# ATMEGA8_PLC.net
KiCad netlist of a schematic drawn in Altium Designer
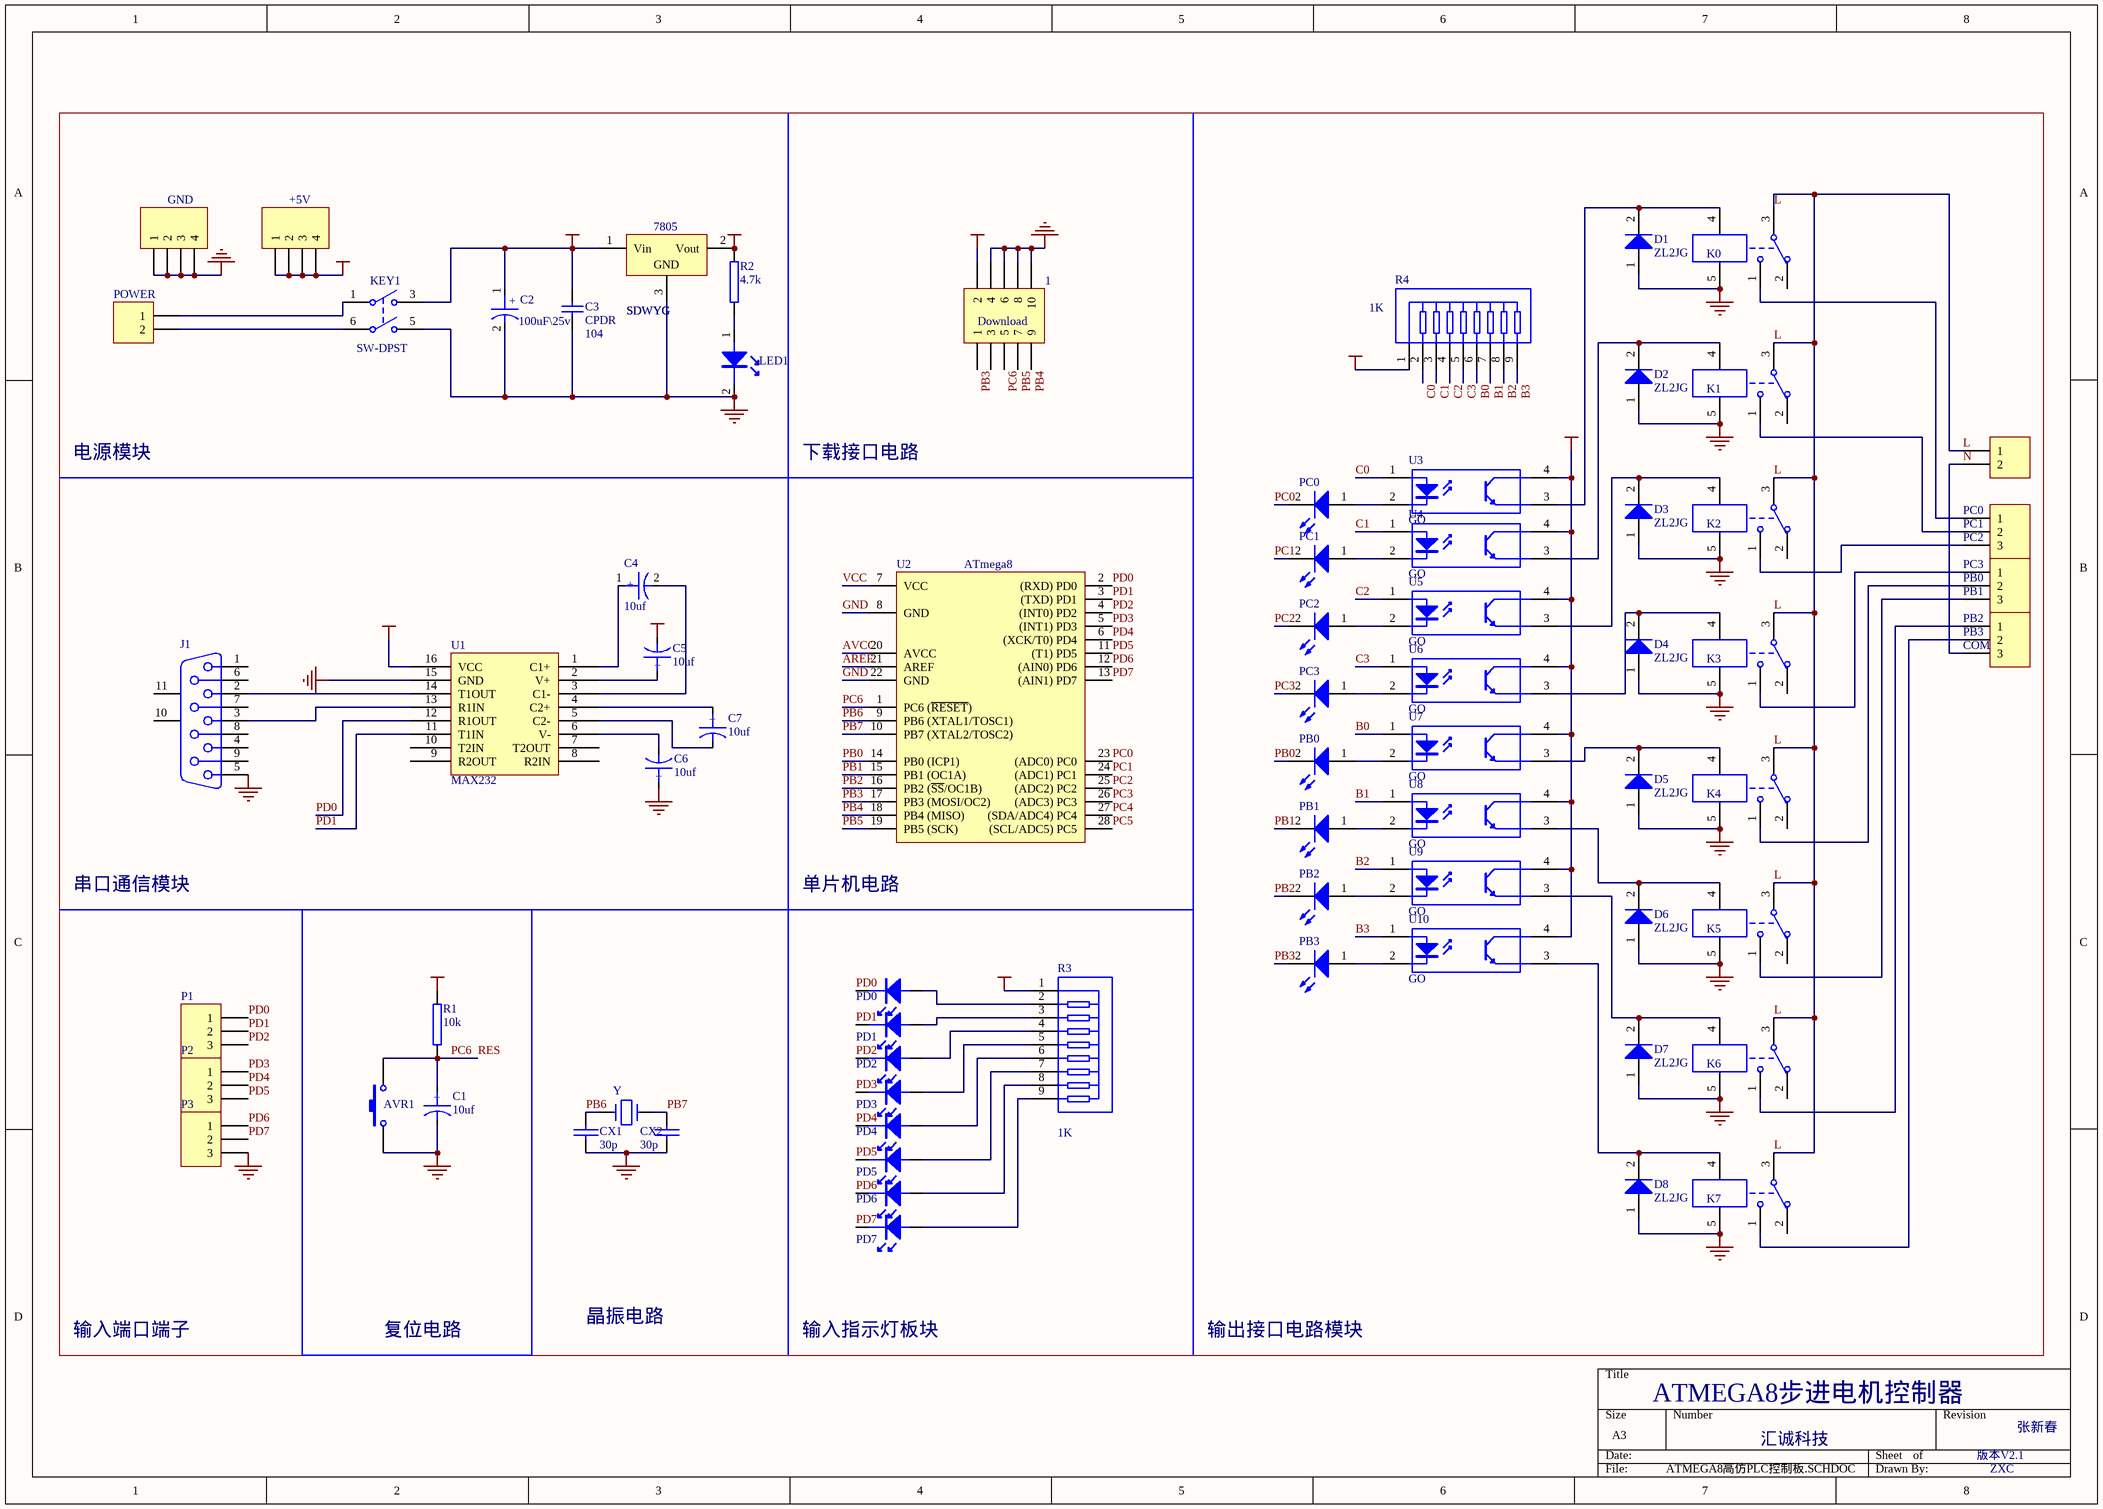
[diagram p0: ATMEGA8高仿PLC控制板.SCHDOC]

(export (version "E")
  (design (tool "Eeschema 10.0.6"))
  (components
    (comp (ref "+5V")
      (value "~")
      (footprint "HDR1X4")
      (description "Header, 4-Pin")
      (fields (field (name "PUBLISHER") "Altium Limited"))
      (libsource (lib "Miscellaneous Connectors") (part "Header 4"))
    )
    (comp (ref "1")
      (value "Download")
      (footprint "HDR-2x5")
      (description "Header, 5-Pin, Dual row")
      (fields (field (name "PUBLISHER") "Altium Limited"))
      (libsource (lib "Miscellaneous Connectors") (part "Header 5X2"))
    )
    (comp (ref "7805")
      (value "SDWYG")
      (footprint "wyk")
      (description "三端稳压器")
      (fields (field (name "PUBLISHER") "Altium Limited"))
      (libsource (lib "zxcourhc") (part "SDWYG"))
    )
    (comp (ref "AVR1")
      (value "~")
      (footprint "an-6*6")
      (description "Switch")
      (fields (field (name "PUBLISHER") "Altium Limited"))
      (libsource (lib "Miscellaneous Devices") (part "SW-PB"))
    )
    (comp (ref "C1")
      (value "10uf")
      (footprint "C-DJ-4")
      (description "Capacitor")
      (libsource (lib "") (part "CAPACITOR POL_1"))
    )
    (comp (ref "C2")
      (value "100u~{F}25v")
      (footprint "C-DJ-6")
      (description "Capacitor")
      (libsource (lib "OldCow1 (1)") (part "CAPACITOR POL"))
    )
    (comp (ref "C3")
      (value "CPDR")
      (footprint "CPDR")
      (description "瓷片电容")
      (fields (field (name "ALTIUM_VALUE") "104") (field (name "PUBLISHER") "Altium Limited"))
      (libsource (lib "zxcourhc") (part "CPDR"))
    )
    (comp (ref "C4")
      (value "10uf")
      (footprint "C-DJ-4")
      (description "Capacitor")
      (libsource (lib "*") (part "CAPACITOR POL"))
    )
    (comp (ref "C5")
      (value "10uf")
      (footprint "C-DJ-4")
      (description "Capacitor")
      (libsource (lib "") (part "CAPACITOR POL_1"))
    )
    (comp (ref "C6")
      (value "10uf")
      (footprint "C-DJ-4")
      (description "Capacitor")
      (libsource (lib "") (part "CAPACITOR POL_1"))
    )
    (comp (ref "C7")
      (value "10uf")
      (footprint "C-DJ-4")
      (description "Capacitor")
      (libsource (lib "") (part "CAPACITOR POL_1"))
    )
    (comp (ref "CX1")
      (value "30p")
      (footprint "HDR1X2")
      (description "Capacitor")
      (libsource (lib "*") (part "CAP"))
    )
    (comp (ref "CX2")
      (value "30p")
      (footprint "HDR1X2")
      (description "Capacitor")
      (libsource (lib "*") (part "CAP"))
    )
    (comp (ref "D1")
      (value "ZL2JG")
      (footprint "D-ZL-10")
      (description "整流二极管")
      (fields (field (name "PUBLISHER") "Altium Limited"))
      (libsource (lib "zxcourhc") (part "ZL2JG"))
    )
    (comp (ref "D2")
      (value "ZL2JG")
      (footprint "D-ZL-10")
      (description "整流二极管")
      (fields (field (name "PUBLISHER") "Altium Limited"))
      (libsource (lib "zxcourhc") (part "ZL2JG"))
    )
    (comp (ref "D3")
      (value "ZL2JG")
      (footprint "D-ZL-10")
      (description "整流二极管")
      (fields (field (name "PUBLISHER") "Altium Limited"))
      (libsource (lib "zxcourhc") (part "ZL2JG"))
    )
    (comp (ref "D4")
      (value "ZL2JG")
      (footprint "D-ZL-10")
      (description "整流二极管")
      (fields (field (name "PUBLISHER") "Altium Limited"))
      (libsource (lib "zxcourhc") (part "ZL2JG"))
    )
    (comp (ref "D5")
      (value "ZL2JG")
      (footprint "D-ZL-10")
      (description "整流二极管")
      (fields (field (name "PUBLISHER") "Altium Limited"))
      (libsource (lib "zxcourhc") (part "ZL2JG"))
    )
    (comp (ref "D6")
      (value "ZL2JG")
      (footprint "D-ZL-10")
      (description "整流二极管")
      (fields (field (name "PUBLISHER") "Altium Limited"))
      (libsource (lib "zxcourhc") (part "ZL2JG"))
    )
    (comp (ref "D7")
      (value "ZL2JG")
      (footprint "D-ZL-10")
      (description "整流二极管")
      (fields (field (name "PUBLISHER") "Altium Limited"))
      (libsource (lib "zxcourhc") (part "ZL2JG"))
    )
    (comp (ref "D8")
      (value "ZL2JG")
      (footprint "D-ZL-10")
      (description "整流二极管")
      (fields (field (name "PUBLISHER") "Altium Limited"))
      (libsource (lib "zxcourhc") (part "ZL2JG"))
    )
    (comp (ref "GND")
      (value "~")
      (footprint "HDR1X4")
      (description "Header, 4-Pin")
      (fields (field (name "PUBLISHER") "Altium Limited"))
      (libsource (lib "Miscellaneous Connectors") (part "Header 4"))
    )
    (comp (ref "J1")
      (value "D Connector 9")
      (footprint "DSUB1.385-2H9")
      (description "Receptacle Assembly, 9 Position, Right Angle")
      (fields (field (name "PUBLISHER") "Altium Limited"))
      (libsource (lib "Miscellaneous Connectors") (part "D Connector 9"))
    )
    (comp (ref "K0")
      (value "JDQYCK")
      (footprint "JQC-3F/T73")
      (description "继电器——1常开1常闭")
      (fields (field (name "PUBLISHER") "Altium Limited"))
      (libsource (lib "zxcourhc") (part "JDQYCK"))
    )
    (comp (ref "K1")
      (value "JDQYCK")
      (footprint "JQC-3F/T73")
      (description "继电器——1常开1常闭")
      (fields (field (name "PUBLISHER") "Altium Limited"))
      (libsource (lib "zxcourhc") (part "JDQYCK"))
    )
    (comp (ref "K2")
      (value "JDQYCK")
      (footprint "JQC-3F/T73")
      (description "继电器——1常开1常闭")
      (fields (field (name "PUBLISHER") "Altium Limited"))
      (libsource (lib "zxcourhc") (part "JDQYCK"))
    )
    (comp (ref "K3")
      (value "JDQYCK")
      (footprint "JQC-3F/T73")
      (description "继电器——1常开1常闭")
      (fields (field (name "PUBLISHER") "Altium Limited"))
      (libsource (lib "zxcourhc") (part "JDQYCK"))
    )
    (comp (ref "K4")
      (value "JDQYCK")
      (footprint "JQC-3F/T73")
      (description "继电器——1常开1常闭")
      (fields (field (name "PUBLISHER") "Altium Limited"))
      (libsource (lib "zxcourhc") (part "JDQYCK"))
    )
    (comp (ref "K5")
      (value "JDQYCK")
      (footprint "JQC-3F/T73")
      (description "继电器——1常开1常闭")
      (fields (field (name "PUBLISHER") "Altium Limited"))
      (libsource (lib "zxcourhc") (part "JDQYCK"))
    )
    (comp (ref "K6")
      (value "JDQYCK")
      (footprint "JQC-3F/T73")
      (description "继电器——1常开1常闭")
      (fields (field (name "PUBLISHER") "Altium Limited"))
      (libsource (lib "zxcourhc") (part "JDQYCK"))
    )
    (comp (ref "K7")
      (value "JDQYCK")
      (footprint "JQC-3F/T73")
      (description "继电器——1常开1常闭")
      (fields (field (name "PUBLISHER") "Altium Limited"))
      (libsource (lib "zxcourhc") (part "JDQYCK"))
    )
    (comp (ref "KEY1")
      (value "SW-DPST")
      (footprint "DPDT-6")
      (description "Double-Pole, Single-Throw Switch")
      (fields (field (name "PUBLISHER") "Altium Limited"))
      (libsource (lib "Miscellaneous Devices") (part "SW-DPST"))
    )
    (comp (ref "LED1") (value "LED") (footprint "LED") (libsource (lib "OldCow1 (1)") (part "LED")))
    (comp (ref "P1")
      (value "PZ_3")
      (footprint "JK128_3")
      (description "排针——3")
      (fields (field (name "PUBLISHER") "Altium Limited"))
      (libsource (lib "zxcourhc") (part "PZ_3"))
    )
    (comp (ref "P2")
      (value "PZ_3")
      (footprint "JK128_3")
      (description "排针——3")
      (fields (field (name "PUBLISHER") "Altium Limited"))
      (libsource (lib "zxcourhc") (part "PZ_3"))
    )
    (comp (ref "P3")
      (value "~")
      (footprint "JK128_3")
      (description "排针——3")
      (fields (field (name "PUBLISHER") "Altium Limited"))
      (libsource (lib "zxcourhc") (part "PZ_3"))
    )
    (comp (ref "P4")
      (value "PZ_2")
      (footprint "DYDZ")
      (description "排针——2")
      (fields (field (name "PUBLISHER") "Altium Limited"))
      (libsource (lib "zxcourhc") (part "PZ_2"))
    )
    (comp (ref "PB0")
      (value "~")
      (footprint "CPDR")
      (description "发光二极管")
      (fields (field (name "PUBLISHER") "Altium Limited"))
      (libsource (lib "zxcourhc") (part "LED"))
    )
    (comp (ref "PB1")
      (value "~")
      (footprint "CPDR")
      (description "发光二极管")
      (fields (field (name "PUBLISHER") "Altium Limited"))
      (libsource (lib "zxcourhc") (part "LED"))
    )
    (comp (ref "PB2")
      (value "~")
      (footprint "CPDR")
      (description "发光二极管")
      (fields (field (name "PUBLISHER") "Altium Limited"))
      (libsource (lib "zxcourhc") (part "LED"))
    )
    (comp (ref "PB3")
      (value "~")
      (footprint "CPDR")
      (description "发光二极管")
      (fields (field (name "PUBLISHER") "Altium Limited"))
      (libsource (lib "zxcourhc") (part "LED"))
    )
    (comp (ref "PC0")
      (value "~")
      (footprint "CPDR")
      (description "发光二极管")
      (fields (field (name "PUBLISHER") "Altium Limited"))
      (libsource (lib "zxcourhc") (part "LED"))
    )
    (comp (ref "PC1")
      (value "~")
      (footprint "CPDR")
      (description "发光二极管")
      (fields (field (name "PUBLISHER") "Altium Limited"))
      (libsource (lib "zxcourhc") (part "LED"))
    )
    (comp (ref "PC2")
      (value "~")
      (footprint "CPDR")
      (description "发光二极管")
      (fields (field (name "PUBLISHER") "Altium Limited"))
      (libsource (lib "zxcourhc") (part "LED"))
    )
    (comp (ref "PC3")
      (value "~")
      (footprint "CPDR")
      (description "发光二极管")
      (fields (field (name "PUBLISHER") "Altium Limited"))
      (libsource (lib "zxcourhc") (part "LED"))
    )
    (comp (ref "PD0") (value "LED") (footprint "HDR1X2") (libsource (lib "") (part "LED_1")))
    (comp (ref "PD1") (value "LED") (footprint "HDR1X2") (libsource (lib "") (part "LED_1")))
    (comp (ref "PD2") (value "LED") (footprint "HDR1X2") (libsource (lib "") (part "LED_1")))
    (comp (ref "PD3") (value "LED") (footprint "HDR1X2") (libsource (lib "") (part "LED_1")))
    (comp (ref "PD4") (value "LED") (footprint "HDR1X2") (libsource (lib "") (part "LED_1")))
    (comp (ref "PD5") (value "LED") (footprint "HDR1X2") (libsource (lib "") (part "LED_1")))
    (comp (ref "PD6") (value "LED") (footprint "HDR1X2") (libsource (lib "") (part "LED_1")))
    (comp (ref "PD7") (value "LED") (footprint "HDR1X2") (libsource (lib "") (part "LED_1")))
    (comp (ref "POUT1")
      (value "PZ_3")
      (footprint "JK128_3")
      (description "排针——3")
      (fields (field (name "PUBLISHER") "Altium Limited"))
      (libsource (lib "") (part "PZ_3_1"))
    )
    (comp (ref "POUT2")
      (value "PZ_3")
      (footprint "JK128_3")
      (description "排针——3")
      (fields (field (name "PUBLISHER") "Altium Limited"))
      (libsource (lib "") (part "PZ_3_1"))
    )
    (comp (ref "POUT3")
      (value "PZ_3")
      (footprint "JK128_3")
      (description "排针——3")
      (fields (field (name "PUBLISHER") "Altium Limited"))
      (libsource (lib "") (part "PZ_3_1"))
    )
    (comp (ref "POWER")
      (value "~")
      (footprint "JK128_2")
      (description "Header, 2-Pin")
      (fields (field (name "PUBLISHER") "Altium Limited"))
      (libsource (lib "Miscellaneous Connectors") (part "Header 2"))
    )
    (comp (ref "R1") (value "10k") (footprint "RSE") (libsource (lib "*") (part "RES2")))
    (comp (ref "R2") (value "4.7k") (footprint "RSE") (libsource (lib "*") (part "RES2")))
    (comp (ref "R3")
      (value "1K")
      (footprint "HDR-10")
      (description "8位排阻")
      (fields (field (name "PUBLISHER") "Altium Limited"))
      (libsource (lib "zxcourhc") (part "Res PZ_8"))
    )
    (comp (ref "R4")
      (value "1K")
      (footprint "HDR-10")
      (description "8位排阻")
      (fields (field (name "PUBLISHER") "Altium Limited"))
      (libsource (lib "zxcourhc") (part "Res PZ_8"))
    )
    (comp (ref "U1") (value "MAX232") (footprint "DIP16") (libsource (lib "*") (part "MAX232")))
    (comp (ref "U2")
      (value "ATmega8")
      (footprint "DIP-28")
      (description "8 位微处理器/28引脚")
      (fields (field (name "发布者") "磊元工作室"))
      (libsource (lib "MCU") (part "ATmega8-P"))
    )
    (comp (ref "U3")
      (value "GO")
      (footprint "DIP-4")
      (description "光耦")
      (fields (field (name "PUBLISHER") "Altium Limited"))
      (libsource (lib "zxcourhc") (part "GO"))
    )
    (comp (ref "U4")
      (value "GO")
      (footprint "DIP-4")
      (description "光耦")
      (fields (field (name "PUBLISHER") "Altium Limited"))
      (libsource (lib "zxcourhc") (part "GO"))
    )
    (comp (ref "U5")
      (value "GO")
      (footprint "DIP-4")
      (description "光耦")
      (fields (field (name "PUBLISHER") "Altium Limited"))
      (libsource (lib "zxcourhc") (part "GO"))
    )
    (comp (ref "U6")
      (value "GO")
      (footprint "DIP-4")
      (description "光耦")
      (fields (field (name "PUBLISHER") "Altium Limited"))
      (libsource (lib "zxcourhc") (part "GO"))
    )
    (comp (ref "U7")
      (value "GO")
      (footprint "DIP-4")
      (description "光耦")
      (fields (field (name "PUBLISHER") "Altium Limited"))
      (libsource (lib "zxcourhc") (part "GO"))
    )
    (comp (ref "U8")
      (value "GO")
      (footprint "DIP-4")
      (description "光耦")
      (fields (field (name "PUBLISHER") "Altium Limited"))
      (libsource (lib "zxcourhc") (part "GO"))
    )
    (comp (ref "U9")
      (value "GO")
      (footprint "DIP-4")
      (description "光耦")
      (fields (field (name "PUBLISHER") "Altium Limited"))
      (libsource (lib "zxcourhc") (part "GO"))
    )
    (comp (ref "U10")
      (value "GO")
      (footprint "DIP-4")
      (description "光耦")
      (fields (field (name "PUBLISHER") "Altium Limited"))
      (libsource (lib "zxcourhc") (part "GO"))
    )
    (comp (ref "Y1")
      (value "Y")
      (footprint "JZ_ZC")
      (description "Crystal")
      (libsource (lib "*") (part "CRYSTAL"))
    )
  )
  (nets
    (net (code "1") (name "+12V") (class "Default")
      (node (ref "7805") (pin "1") (pinfunction "Vin_1") (pintype "passive"))
      (node (ref "C2") (pin "1") (pinfunction "1_1") (pintype "passive"))
      (node (ref "C3") (pin "2") (pinfunction "2_2") (pintype "passive"))
      (node (ref "KEY1") (pin "3") (pinfunction "NO1_3") (pintype "passive"))
      (node (ref "U10") (pin "4") (pinfunction "C_4") (pintype "passive"))
      (node (ref "U3") (pin "4") (pinfunction "C_4") (pintype "passive"))
      (node (ref "U4") (pin "4") (pinfunction "C_4") (pintype "passive"))
      (node (ref "U5") (pin "4") (pinfunction "C_4") (pintype "passive"))
      (node (ref "U6") (pin "4") (pinfunction "C_4") (pintype "passive"))
      (node (ref "U7") (pin "4") (pinfunction "C_4") (pintype "passive"))
      (node (ref "U8") (pin "4") (pinfunction "C_4") (pintype "passive"))
      (node (ref "U9") (pin "4") (pinfunction "C_4") (pintype "passive"))
    )
    (net (code "2") (name "/AREF") (class "Default")
      (node (ref "U2") (pin "21") (pinfunction "AREF_21") (pintype "passive"))
    )
    (net (code "3") (name "/AVCC") (class "Default")
      (node (ref "U2") (pin "20") (pinfunction "AVCC_20") (pintype "passive"))
    )
    (net (code "4") (name "/B0") (class "Default")
      (node (ref "R4") (pin "6") (pinfunction "6_6") (pintype "passive"))
      (node (ref "U7") (pin "1") (pinfunction "A_1") (pintype "passive"))
    )
    (net (code "5") (name "/B1") (class "Default")
      (node (ref "R4") (pin "7") (pinfunction "7_7") (pintype "passive"))
      (node (ref "U8") (pin "1") (pinfunction "A_1") (pintype "passive"))
    )
    (net (code "6") (name "/B2") (class "Default")
      (node (ref "R4") (pin "8") (pinfunction "8_8") (pintype "passive"))
      (node (ref "U9") (pin "1") (pinfunction "A_1") (pintype "passive"))
    )
    (net (code "7") (name "/B3") (class "Default")
      (node (ref "R4") (pin "9") (pinfunction "9_9") (pintype "passive"))
      (node (ref "U10") (pin "1") (pinfunction "A_1") (pintype "passive"))
    )
    (net (code "8") (name "/C0") (class "Default")
      (node (ref "R4") (pin "2") (pinfunction "2_2") (pintype "passive"))
      (node (ref "U3") (pin "1") (pinfunction "A_1") (pintype "passive"))
    )
    (net (code "9") (name "/C1") (class "Default")
      (node (ref "R4") (pin "3") (pinfunction "3_3") (pintype "passive"))
      (node (ref "U4") (pin "1") (pinfunction "A_1") (pintype "passive"))
    )
    (net (code "10") (name "/C2") (class "Default")
      (node (ref "R4") (pin "4") (pinfunction "4_4") (pintype "passive"))
      (node (ref "U5") (pin "1") (pinfunction "A_1") (pintype "passive"))
    )
    (net (code "11") (name "/C3") (class "Default")
      (node (ref "R4") (pin "5") (pinfunction "5_5") (pintype "passive"))
      (node (ref "U6") (pin "1") (pinfunction "A_1") (pintype "passive"))
    )
    (net (code "12") (name "/L") (class "Default")
      (node (ref "K0") (pin "3") (pinfunction "3_3") (pintype "passive"))
      (node (ref "K1") (pin "3") (pinfunction "3_3") (pintype "passive"))
      (node (ref "K2") (pin "3") (pinfunction "3_3") (pintype "passive"))
      (node (ref "K3") (pin "3") (pinfunction "3_3") (pintype "passive"))
      (node (ref "K4") (pin "3") (pinfunction "3_3") (pintype "passive"))
      (node (ref "K5") (pin "3") (pinfunction "3_3") (pintype "passive"))
      (node (ref "K6") (pin "3") (pinfunction "3_3") (pintype "passive"))
      (node (ref "K7") (pin "3") (pinfunction "3_3") (pintype "passive"))
      (node (ref "P4") (pin "1") (pinfunction "1_1") (pintype "passive"))
    )
    (net (code "13") (name "/N") (class "Default")
      (node (ref "P4") (pin "2") (pinfunction "2_2") (pintype "passive"))
      (node (ref "POUT3") (pin "3") (pinfunction "3_3") (pintype "passive"))
    )
    (net (code "14") (name "/PB0") (class "Default")
      (node (ref "PB0") (pin "2") (pinfunction "K_2") (pintype "passive"))
      (node (ref "U2") (pin "14") (pinfunction "PB0_(ICP1)_14") (pintype "passive"))
    )
    (net (code "15") (name "/PB1") (class "Default")
      (node (ref "PB1") (pin "2") (pinfunction "K_2") (pintype "passive"))
      (node (ref "U2") (pin "15") (pinfunction "PB1_(OC1A)_15") (pintype "passive"))
    )
    (net (code "16") (name "/PB2") (class "Default")
      (node (ref "PB2") (pin "2") (pinfunction "K_2") (pintype "passive"))
      (node (ref "U2") (pin "16") (pinfunction "PB2_(~{SS}/OC1B)_16") (pintype "passive"))
    )
    (net (code "17") (name "/PB3") (class "Default")
      (node (ref "1") (pin "1") (pinfunction "1_1") (pintype "passive"))
      (node (ref "PB3") (pin "2") (pinfunction "K_2") (pintype "passive"))
      (node (ref "U2") (pin "17") (pinfunction "PB3_(MOSI/OC2)_17") (pintype "passive"))
    )
    (net (code "18") (name "/PB4") (class "Default")
      (node (ref "1") (pin "9") (pinfunction "9_9") (pintype "passive"))
      (node (ref "U2") (pin "18") (pinfunction "PB4_(MISO)_18") (pintype "passive"))
    )
    (net (code "19") (name "/PB5") (class "Default")
      (node (ref "1") (pin "7") (pinfunction "7_7") (pintype "passive"))
      (node (ref "U2") (pin "19") (pinfunction "PB5_(SCK)_19") (pintype "passive"))
    )
    (net (code "20") (name "/PB6") (class "Default")
      (node (ref "CX1") (pin "1") (pinfunction "1_1") (pintype "passive"))
      (node (ref "U2") (pin "9") (pinfunction "PB6_(XTAL1/TOSC1)_9") (pintype "passive"))
      (node (ref "Y1") (pin "2") (pinfunction "2_2") (pintype "passive"))
    )
    (net (code "21") (name "/PB7") (class "Default")
      (node (ref "CX2") (pin "1") (pinfunction "1_1") (pintype "passive"))
      (node (ref "U2") (pin "10") (pinfunction "PB7_(XTAL2/TOSC2)_10") (pintype "passive"))
      (node (ref "Y1") (pin "1") (pinfunction "1_1") (pintype "passive"))
    )
    (net (code "22") (name "/PC0") (class "Default")
      (node (ref "PC0") (pin "2") (pinfunction "K_2") (pintype "passive"))
      (node (ref "U2") (pin "23") (pinfunction "(ADC0)_PC0_23") (pintype "passive"))
    )
    (net (code "23") (name "/PC1") (class "Default")
      (node (ref "PC1") (pin "2") (pinfunction "K_2") (pintype "passive"))
      (node (ref "U2") (pin "24") (pinfunction "(ADC1)_PC1_24") (pintype "passive"))
    )
    (net (code "24") (name "/PC2") (class "Default")
      (node (ref "PC2") (pin "2") (pinfunction "K_2") (pintype "passive"))
      (node (ref "U2") (pin "25") (pinfunction "(ADC2)_PC2_25") (pintype "passive"))
    )
    (net (code "25") (name "/PC3") (class "Default")
      (node (ref "PC3") (pin "2") (pinfunction "K_2") (pintype "passive"))
      (node (ref "U2") (pin "26") (pinfunction "(ADC3)_PC3_26") (pintype "passive"))
    )
    (net (code "26") (name "/PC4") (class "Default")
      (node (ref "U2") (pin "27") (pinfunction "(SDA/ADC4)_PC4_27") (pintype "passive"))
    )
    (net (code "27") (name "/PC5") (class "Default")
      (node (ref "U2") (pin "28") (pinfunction "(SCL/ADC5)_PC5_28") (pintype "passive"))
    )
    (net (code "28") (name "/PC6") (class "Default")
      (node (ref "1") (pin "5") (pinfunction "5_5") (pintype "passive"))
      (node (ref "AVR1") (pin "1") (pinfunction "1_1") (pintype "passive"))
      (node (ref "C1") (pin "1") (pinfunction "1_1") (pintype "passive"))
      (node (ref "R1") (pin "1") (pinfunction "1_1") (pintype "passive"))
      (node (ref "U2") (pin "1") (pinfunction "PC6_(~{RESET})_1") (pintype "passive"))
    )
    (net (code "29") (name "/PD0") (class "Default")
      (node (ref "P1") (pin "1") (pinfunction "1_1") (pintype "passive"))
      (node (ref "PD0") (pin "2") (pinfunction "K_2") (pintype "passive"))
      (node (ref "U1") (pin "12") (pinfunction "R1OUT_12") (pintype "passive"))
      (node (ref "U2") (pin "2") (pinfunction "(RXD)_PD0_2") (pintype "passive"))
    )
    (net (code "30") (name "/PD1") (class "Default")
      (node (ref "P1") (pin "2") (pinfunction "2_2") (pintype "passive"))
      (node (ref "PD1") (pin "2") (pinfunction "K_2") (pintype "passive"))
      (node (ref "U1") (pin "11") (pinfunction "T1IN_11") (pintype "passive"))
      (node (ref "U2") (pin "3") (pinfunction "(TXD)_PD1_3") (pintype "passive"))
    )
    (net (code "31") (name "/PD2") (class "Default")
      (node (ref "P1") (pin "3") (pinfunction "3_3") (pintype "passive"))
      (node (ref "PD2") (pin "2") (pinfunction "K_2") (pintype "passive"))
      (node (ref "U2") (pin "4") (pinfunction "(INT0)_PD2_4") (pintype "passive"))
    )
    (net (code "32") (name "/PD3") (class "Default")
      (node (ref "P2") (pin "1") (pinfunction "1_1") (pintype "passive"))
      (node (ref "PD3") (pin "2") (pinfunction "K_2") (pintype "passive"))
      (node (ref "U2") (pin "5") (pinfunction "(INT1)_PD3_5") (pintype "passive"))
    )
    (net (code "33") (name "/PD4") (class "Default")
      (node (ref "P2") (pin "2") (pinfunction "2_2") (pintype "passive"))
      (node (ref "PD4") (pin "2") (pinfunction "K_2") (pintype "passive"))
      (node (ref "U2") (pin "6") (pinfunction "(XCK/T0)_PD4_6") (pintype "passive"))
    )
    (net (code "34") (name "/PD5") (class "Default")
      (node (ref "P2") (pin "3") (pinfunction "3_3") (pintype "passive"))
      (node (ref "PD5") (pin "2") (pinfunction "K_2") (pintype "passive"))
      (node (ref "U2") (pin "11") (pinfunction "(T1)_PD5_11") (pintype "passive"))
    )
    (net (code "35") (name "/PD6") (class "Default")
      (node (ref "P3") (pin "1") (pinfunction "1_1") (pintype "passive"))
      (node (ref "PD6") (pin "2") (pinfunction "K_2") (pintype "passive"))
      (node (ref "U2") (pin "12") (pinfunction "(AIN0)_PD6_12") (pintype "passive"))
    )
    (net (code "36") (name "/PD7") (class "Default")
      (node (ref "P3") (pin "2") (pinfunction "2_2") (pintype "passive"))
      (node (ref "PD7") (pin "2") (pinfunction "K_2") (pintype "passive"))
      (node (ref "U2") (pin "13") (pinfunction "(AIN1)_PD7_13") (pintype "passive"))
    )
    (net (code "37") (name "GND") (class "Default")
      (node (ref "1") (pin "10") (pinfunction "10_10") (pintype "passive"))
      (node (ref "1") (pin "4") (pinfunction "4_4") (pintype "passive"))
      (node (ref "1") (pin "6") (pinfunction "6_6") (pintype "passive"))
      (node (ref "1") (pin "8") (pinfunction "8_8") (pintype "passive"))
      (node (ref "7805") (pin "3") (pinfunction "GND_3") (pintype "passive"))
      (node (ref "AVR1") (pin "2") (pinfunction "2_2") (pintype "passive"))
      (node (ref "C1") (pin "2") (pinfunction "2_2") (pintype "passive"))
      (node (ref "C2") (pin "2") (pinfunction "2_2") (pintype "passive"))
      (node (ref "C3") (pin "1") (pinfunction "1_1") (pintype "passive"))
      (node (ref "C6") (pin "1") (pinfunction "1_1") (pintype "passive"))
      (node (ref "CX1") (pin "2") (pinfunction "2_2") (pintype "passive"))
      (node (ref "CX2") (pin "2") (pinfunction "2_2") (pintype "passive"))
      (node (ref "D1") (pin "1") (pinfunction "A_1") (pintype "passive"))
      (node (ref "D2") (pin "1") (pinfunction "A_1") (pintype "passive"))
      (node (ref "D3") (pin "1") (pinfunction "A_1") (pintype "passive"))
      (node (ref "D4") (pin "1") (pinfunction "A_1") (pintype "passive"))
      (node (ref "D5") (pin "1") (pinfunction "A_1") (pintype "passive"))
      (node (ref "D6") (pin "1") (pinfunction "A_1") (pintype "passive"))
      (node (ref "D7") (pin "1") (pinfunction "A_1") (pintype "passive"))
      (node (ref "D8") (pin "1") (pinfunction "A_1") (pintype "passive"))
      (node (ref "GND") (pin "1") (pinfunction "1_1") (pintype "passive"))
      (node (ref "GND") (pin "2") (pinfunction "2_2") (pintype "passive"))
      (node (ref "GND") (pin "3") (pinfunction "3_3") (pintype "passive"))
      (node (ref "GND") (pin "4") (pinfunction "4_4") (pintype "passive"))
      (node (ref "J1") (pin "5") (pinfunction "5_5") (pintype "passive"))
      (node (ref "K0") (pin "5") (pinfunction "5_5") (pintype "passive"))
      (node (ref "K1") (pin "5") (pinfunction "5_5") (pintype "passive"))
      (node (ref "K2") (pin "5") (pinfunction "5_5") (pintype "passive"))
      (node (ref "K3") (pin "5") (pinfunction "5_5") (pintype "passive"))
      (node (ref "K4") (pin "5") (pinfunction "5_5") (pintype "passive"))
      (node (ref "K5") (pin "5") (pinfunction "5_5") (pintype "passive"))
      (node (ref "K6") (pin "5") (pinfunction "5_5") (pintype "passive"))
      (node (ref "K7") (pin "5") (pinfunction "5_5") (pintype "passive"))
      (node (ref "KEY1") (pin "5") (pinfunction "NO2_5") (pintype "passive"))
      (node (ref "LED1") (pin "2") (pinfunction "K_2") (pintype "passive"))
      (node (ref "P3") (pin "3") (pinfunction "3_3") (pintype "passive"))
      (node (ref "U1") (pin "15") (pinfunction "GND_15") (pintype "passive"))
      (node (ref "U2") (pin "22") (pinfunction "GND_22") (pintype "passive"))
      (node (ref "U2") (pin "8") (pinfunction "GND_8") (pintype "passive"))
    )
    (net (code "38") (name "Net-(D1-K)") (class "Default")
      (node (ref "D1") (pin "2") (pinfunction "K_2") (pintype "passive"))
      (node (ref "K0") (pin "4") (pinfunction "4_4") (pintype "passive"))
      (node (ref "U3") (pin "3") (pinfunction "E_3") (pintype "passive"))
    )
    (net (code "39") (name "Net-(D2-K)") (class "Default")
      (node (ref "D2") (pin "2") (pinfunction "K_2") (pintype "passive"))
      (node (ref "K1") (pin "4") (pinfunction "4_4") (pintype "passive"))
      (node (ref "U4") (pin "3") (pinfunction "E_3") (pintype "passive"))
    )
    (net (code "40") (name "Net-(D3-K)") (class "Default")
      (node (ref "D3") (pin "2") (pinfunction "K_2") (pintype "passive"))
      (node (ref "K2") (pin "4") (pinfunction "4_4") (pintype "passive"))
      (node (ref "U5") (pin "3") (pinfunction "E_3") (pintype "passive"))
    )
    (net (code "41") (name "Net-(D4-K)") (class "Default")
      (node (ref "D4") (pin "2") (pinfunction "K_2") (pintype "passive"))
      (node (ref "K3") (pin "4") (pinfunction "4_4") (pintype "passive"))
      (node (ref "U6") (pin "3") (pinfunction "E_3") (pintype "passive"))
    )
    (net (code "42") (name "Net-(D5-K)") (class "Default")
      (node (ref "D5") (pin "2") (pinfunction "K_2") (pintype "passive"))
      (node (ref "K4") (pin "4") (pinfunction "4_4") (pintype "passive"))
      (node (ref "U7") (pin "3") (pinfunction "E_3") (pintype "passive"))
    )
    (net (code "43") (name "Net-(D6-K)") (class "Default")
      (node (ref "D6") (pin "2") (pinfunction "K_2") (pintype "passive"))
      (node (ref "K5") (pin "4") (pinfunction "4_4") (pintype "passive"))
      (node (ref "U8") (pin "3") (pinfunction "E_3") (pintype "passive"))
    )
    (net (code "44") (name "Net-(D7-K)") (class "Default")
      (node (ref "D7") (pin "2") (pinfunction "K_2") (pintype "passive"))
      (node (ref "K6") (pin "4") (pinfunction "4_4") (pintype "passive"))
      (node (ref "U9") (pin "3") (pinfunction "E_3") (pintype "passive"))
    )
    (net (code "45") (name "Net-(D8-K)") (class "Default")
      (node (ref "D8") (pin "2") (pinfunction "K_2") (pintype "passive"))
      (node (ref "K7") (pin "4") (pinfunction "4_4") (pintype "passive"))
      (node (ref "U10") (pin "3") (pinfunction "E_3") (pintype "passive"))
    )
    (net (code "46") (name "Net-(K0-Pad1)") (class "Default")
      (node (ref "K0") (pin "1") (pinfunction "1_1") (pintype "passive"))
      (node (ref "POUT1") (pin "1") (pinfunction "1_1") (pintype "passive"))
    )
    (net (code "47") (name "Net-(K1-Pad1)") (class "Default")
      (node (ref "K1") (pin "1") (pinfunction "1_1") (pintype "passive"))
      (node (ref "POUT1") (pin "2") (pinfunction "2_2") (pintype "passive"))
    )
    (net (code "48") (name "Net-(K2-Pad1)") (class "Default")
      (node (ref "K2") (pin "1") (pinfunction "1_1") (pintype "passive"))
      (node (ref "POUT1") (pin "3") (pinfunction "3_3") (pintype "passive"))
    )
    (net (code "49") (name "Net-(K3-Pad1)") (class "Default")
      (node (ref "K3") (pin "1") (pinfunction "1_1") (pintype "passive"))
      (node (ref "POUT2") (pin "1") (pinfunction "1_1") (pintype "passive"))
    )
    (net (code "50") (name "Net-(K4-Pad1)") (class "Default")
      (node (ref "K4") (pin "1") (pinfunction "1_1") (pintype "passive"))
      (node (ref "POUT2") (pin "2") (pinfunction "2_2") (pintype "passive"))
    )
    (net (code "51") (name "Net-(K5-Pad1)") (class "Default")
      (node (ref "K5") (pin "1") (pinfunction "1_1") (pintype "passive"))
      (node (ref "POUT2") (pin "3") (pinfunction "3_3") (pintype "passive"))
    )
    (net (code "52") (name "Net-(K6-Pad1)") (class "Default")
      (node (ref "K6") (pin "1") (pinfunction "1_1") (pintype "passive"))
      (node (ref "POUT3") (pin "1") (pinfunction "1_1") (pintype "passive"))
    )
    (net (code "53") (name "Net-(K7-Pad1)") (class "Default")
      (node (ref "K7") (pin "1") (pinfunction "1_1") (pintype "passive"))
      (node (ref "POUT3") (pin "2") (pinfunction "2_2") (pintype "passive"))
    )
    (net (code "54") (name "Net-(KEY1-COMMON1)") (class "Default")
      (node (ref "KEY1") (pin "1") (pinfunction "COMMON1_1") (pintype "passive"))
      (node (ref "POWER") (pin "1") (pinfunction "1_1") (pintype "passive"))
    )
    (net (code "55") (name "Net-(KEY1-COMMON2)") (class "Default")
      (node (ref "KEY1") (pin "6") (pinfunction "COMMON2_6") (pintype "passive"))
      (node (ref "POWER") (pin "2") (pinfunction "2_2") (pintype "passive"))
    )
    (net (code "56") (name "Net-(LED1-A)") (class "Default")
      (node (ref "LED1") (pin "1") (pinfunction "A_1") (pintype "passive"))
      (node (ref "R2") (pin "2") (pinfunction "2_2") (pintype "passive"))
    )
    (net (code "57") (name "Net-(PB0-A)") (class "Default")
      (node (ref "PB0") (pin "1") (pinfunction "A_1") (pintype "passive"))
      (node (ref "U7") (pin "2") (pinfunction "K_2") (pintype "passive"))
    )
    (net (code "58") (name "Net-(PB1-A)") (class "Default")
      (node (ref "PB1") (pin "1") (pinfunction "A_1") (pintype "passive"))
      (node (ref "U8") (pin "2") (pinfunction "K_2") (pintype "passive"))
    )
    (net (code "59") (name "Net-(PB2-A)") (class "Default")
      (node (ref "PB2") (pin "1") (pinfunction "A_1") (pintype "passive"))
      (node (ref "U9") (pin "2") (pinfunction "K_2") (pintype "passive"))
    )
    (net (code "60") (name "Net-(PB3-A)") (class "Default")
      (node (ref "PB3") (pin "1") (pinfunction "A_1") (pintype "passive"))
      (node (ref "U10") (pin "2") (pinfunction "K_2") (pintype "passive"))
    )
    (net (code "61") (name "Net-(PC0-A)") (class "Default")
      (node (ref "PC0") (pin "1") (pinfunction "A_1") (pintype "passive"))
      (node (ref "U3") (pin "2") (pinfunction "K_2") (pintype "passive"))
    )
    (net (code "62") (name "Net-(PC1-A)") (class "Default")
      (node (ref "PC1") (pin "1") (pinfunction "A_1") (pintype "passive"))
      (node (ref "U4") (pin "2") (pinfunction "K_2") (pintype "passive"))
    )
    (net (code "63") (name "Net-(PC2-A)") (class "Default")
      (node (ref "PC2") (pin "1") (pinfunction "A_1") (pintype "passive"))
      (node (ref "U5") (pin "2") (pinfunction "K_2") (pintype "passive"))
    )
    (net (code "64") (name "Net-(PC3-A)") (class "Default")
      (node (ref "PC3") (pin "1") (pinfunction "A_1") (pintype "passive"))
      (node (ref "U6") (pin "2") (pinfunction "K_2") (pintype "passive"))
    )
    (net (code "65") (name "Net-(PD0-A)") (class "Default")
      (node (ref "PD0") (pin "1") (pinfunction "A_1") (pintype "passive"))
      (node (ref "R3") (pin "2") (pinfunction "2_2") (pintype "passive"))
    )
    (net (code "66") (name "Net-(PD1-A)") (class "Default")
      (node (ref "PD1") (pin "1") (pinfunction "A_1") (pintype "passive"))
      (node (ref "R3") (pin "3") (pinfunction "3_3") (pintype "passive"))
    )
    (net (code "67") (name "Net-(PD2-A)") (class "Default")
      (node (ref "PD2") (pin "1") (pinfunction "A_1") (pintype "passive"))
      (node (ref "R3") (pin "4") (pinfunction "4_4") (pintype "passive"))
    )
    (net (code "68") (name "Net-(PD3-A)") (class "Default")
      (node (ref "PD3") (pin "1") (pinfunction "A_1") (pintype "passive"))
      (node (ref "R3") (pin "5") (pinfunction "5_5") (pintype "passive"))
    )
    (net (code "69") (name "Net-(PD4-A)") (class "Default")
      (node (ref "PD4") (pin "1") (pinfunction "A_1") (pintype "passive"))
      (node (ref "R3") (pin "6") (pinfunction "6_6") (pintype "passive"))
    )
    (net (code "70") (name "Net-(PD5-A)") (class "Default")
      (node (ref "PD5") (pin "1") (pinfunction "A_1") (pintype "passive"))
      (node (ref "R3") (pin "7") (pinfunction "7_7") (pintype "passive"))
    )
    (net (code "71") (name "Net-(PD6-A)") (class "Default")
      (node (ref "PD6") (pin "1") (pinfunction "A_1") (pintype "passive"))
      (node (ref "R3") (pin "8") (pinfunction "8_8") (pintype "passive"))
    )
    (net (code "72") (name "Net-(PD7-A)") (class "Default")
      (node (ref "PD7") (pin "1") (pinfunction "A_1") (pintype "passive"))
      (node (ref "R3") (pin "9") (pinfunction "9_9") (pintype "passive"))
    )
    (net (code "73") (name "Net-(U1-C1+)") (class "Default")
      (node (ref "C4") (pin "1") (pinfunction "1_1") (pintype "passive"))
      (node (ref "U1") (pin "1") (pinfunction "C1+_1") (pintype "passive"))
    )
    (net (code "74") (name "Net-(U1-C1-)") (class "Default")
      (node (ref "C4") (pin "2") (pinfunction "2_2") (pintype "passive"))
      (node (ref "U1") (pin "3") (pinfunction "C1-_3") (pintype "passive"))
    )
    (net (code "75") (name "Net-(U1-C2+)") (class "Default")
      (node (ref "C7") (pin "1") (pinfunction "1_1") (pintype "passive"))
      (node (ref "U1") (pin "4") (pinfunction "C2+_4") (pintype "passive"))
    )
    (net (code "76") (name "Net-(U1-C2-)") (class "Default")
      (node (ref "C7") (pin "2") (pinfunction "2_2") (pintype "passive"))
      (node (ref "U1") (pin "5") (pinfunction "C2-_5") (pintype "passive"))
    )
    (net (code "77") (name "Net-(U1-R1IN)") (class "Default")
      (node (ref "J1") (pin "3") (pinfunction "3_3") (pintype "passive"))
      (node (ref "U1") (pin "13") (pinfunction "R1IN_13") (pintype "passive"))
    )
    (net (code "78") (name "Net-(U1-T1OUT)") (class "Default")
      (node (ref "J1") (pin "2") (pinfunction "2_2") (pintype "passive"))
      (node (ref "U1") (pin "14") (pinfunction "T1OUT_14") (pintype "passive"))
    )
    (net (code "79") (name "Net-(U1-V+)") (class "Default")
      (node (ref "C5") (pin "1") (pinfunction "1_1") (pintype "passive"))
      (node (ref "U1") (pin "2") (pinfunction "V+_2") (pintype "passive"))
    )
    (net (code "80") (name "Net-(U1-V-)") (class "Default")
      (node (ref "C6") (pin "2") (pinfunction "2_2") (pintype "passive"))
      (node (ref "U1") (pin "6") (pinfunction "V-_6") (pintype "passive"))
    )
    (net (code "81") (name "VCC") (class "Default")
      (node (ref "+5V") (pin "1") (pinfunction "1_1") (pintype "passive"))
      (node (ref "+5V") (pin "2") (pinfunction "2_2") (pintype "passive"))
      (node (ref "+5V") (pin "3") (pinfunction "3_3") (pintype "passive"))
      (node (ref "+5V") (pin "4") (pinfunction "4_4") (pintype "passive"))
      (node (ref "1") (pin "2") (pinfunction "2_2") (pintype "passive"))
      (node (ref "7805") (pin "2") (pinfunction "Vout_2") (pintype "passive"))
      (node (ref "C5") (pin "2") (pinfunction "2_2") (pintype "passive"))
      (node (ref "R1") (pin "2") (pinfunction "2_2") (pintype "passive"))
      (node (ref "R2") (pin "1") (pinfunction "1_1") (pintype "passive"))
      (node (ref "R3") (pin "1") (pinfunction "1_1") (pintype "passive"))
      (node (ref "R4") (pin "1") (pinfunction "1_1") (pintype "passive"))
      (node (ref "U1") (pin "16") (pinfunction "VCC_16") (pintype "passive"))
      (node (ref "U2") (pin "7") (pinfunction "VCC_7") (pintype "passive"))
    )
    (net (code "82") (name "unconnected-(1-Pad3)") (class "Default")
      (node (ref "1") (pin "3") (pinfunction "3_3") (pintype "passive"))
    )
    (net (code "83") (name "unconnected-(J1-MH1-Pad10)") (class "Default")
      (node (ref "J1") (pin "10") (pinfunction "MH1_10") (pintype "passive"))
    )
    (net (code "84") (name "unconnected-(J1-MH2-Pad11)") (class "Default")
      (node (ref "J1") (pin "11") (pinfunction "MH2_11") (pintype "passive"))
    )
    (net (code "85") (name "unconnected-(J1-Pad1)") (class "Default")
      (node (ref "J1") (pin "1") (pinfunction "1_1") (pintype "passive"))
    )
    (net (code "86") (name "unconnected-(J1-Pad4)") (class "Default")
      (node (ref "J1") (pin "4") (pinfunction "4_4") (pintype "passive"))
    )
    (net (code "87") (name "unconnected-(J1-Pad6)") (class "Default")
      (node (ref "J1") (pin "6") (pinfunction "6_6") (pintype "passive"))
    )
    (net (code "88") (name "unconnected-(J1-Pad7)") (class "Default")
      (node (ref "J1") (pin "7") (pinfunction "7_7") (pintype "passive"))
    )
    (net (code "89") (name "unconnected-(J1-Pad8)") (class "Default")
      (node (ref "J1") (pin "8") (pinfunction "8_8") (pintype "passive"))
    )
    (net (code "90") (name "unconnected-(J1-Pad9)") (class "Default")
      (node (ref "J1") (pin "9") (pinfunction "9_9") (pintype "passive"))
    )
    (net (code "91") (name "unconnected-(K0-Pad2)") (class "Default")
      (node (ref "K0") (pin "2") (pinfunction "2_2") (pintype "passive"))
    )
    (net (code "92") (name "unconnected-(K1-Pad2)") (class "Default")
      (node (ref "K1") (pin "2") (pinfunction "2_2") (pintype "passive"))
    )
    (net (code "93") (name "unconnected-(K2-Pad2)") (class "Default")
      (node (ref "K2") (pin "2") (pinfunction "2_2") (pintype "passive"))
    )
    (net (code "94") (name "unconnected-(K3-Pad2)") (class "Default")
      (node (ref "K3") (pin "2") (pinfunction "2_2") (pintype "passive"))
    )
    (net (code "95") (name "unconnected-(K4-Pad2)") (class "Default")
      (node (ref "K4") (pin "2") (pinfunction "2_2") (pintype "passive"))
    )
    (net (code "96") (name "unconnected-(K5-Pad2)") (class "Default")
      (node (ref "K5") (pin "2") (pinfunction "2_2") (pintype "passive"))
    )
    (net (code "97") (name "unconnected-(K6-Pad2)") (class "Default")
      (node (ref "K6") (pin "2") (pinfunction "2_2") (pintype "passive"))
    )
    (net (code "98") (name "unconnected-(K7-Pad2)") (class "Default")
      (node (ref "K7") (pin "2") (pinfunction "2_2") (pintype "passive"))
    )
    (net (code "99") (name "unconnected-(U1-R2IN-Pad8)") (class "Default")
      (node (ref "U1") (pin "8") (pinfunction "R2IN_8") (pintype "passive"))
    )
    (net (code "100") (name "unconnected-(U1-R2OUT-Pad9)") (class "Default")
      (node (ref "U1") (pin "9") (pinfunction "R2OUT_9") (pintype "passive"))
    )
    (net (code "101") (name "unconnected-(U1-T2IN-Pad10)") (class "Default")
      (node (ref "U1") (pin "10") (pinfunction "T2IN_10") (pintype "passive"))
    )
    (net (code "102") (name "unconnected-(U1-T2OUT-Pad7)") (class "Default")
      (node (ref "U1") (pin "7") (pinfunction "T2OUT_7") (pintype "passive"))
    )
  )
)
